# Peripherals.net
KiCad netlist of a schematic drawn in Altium Designer
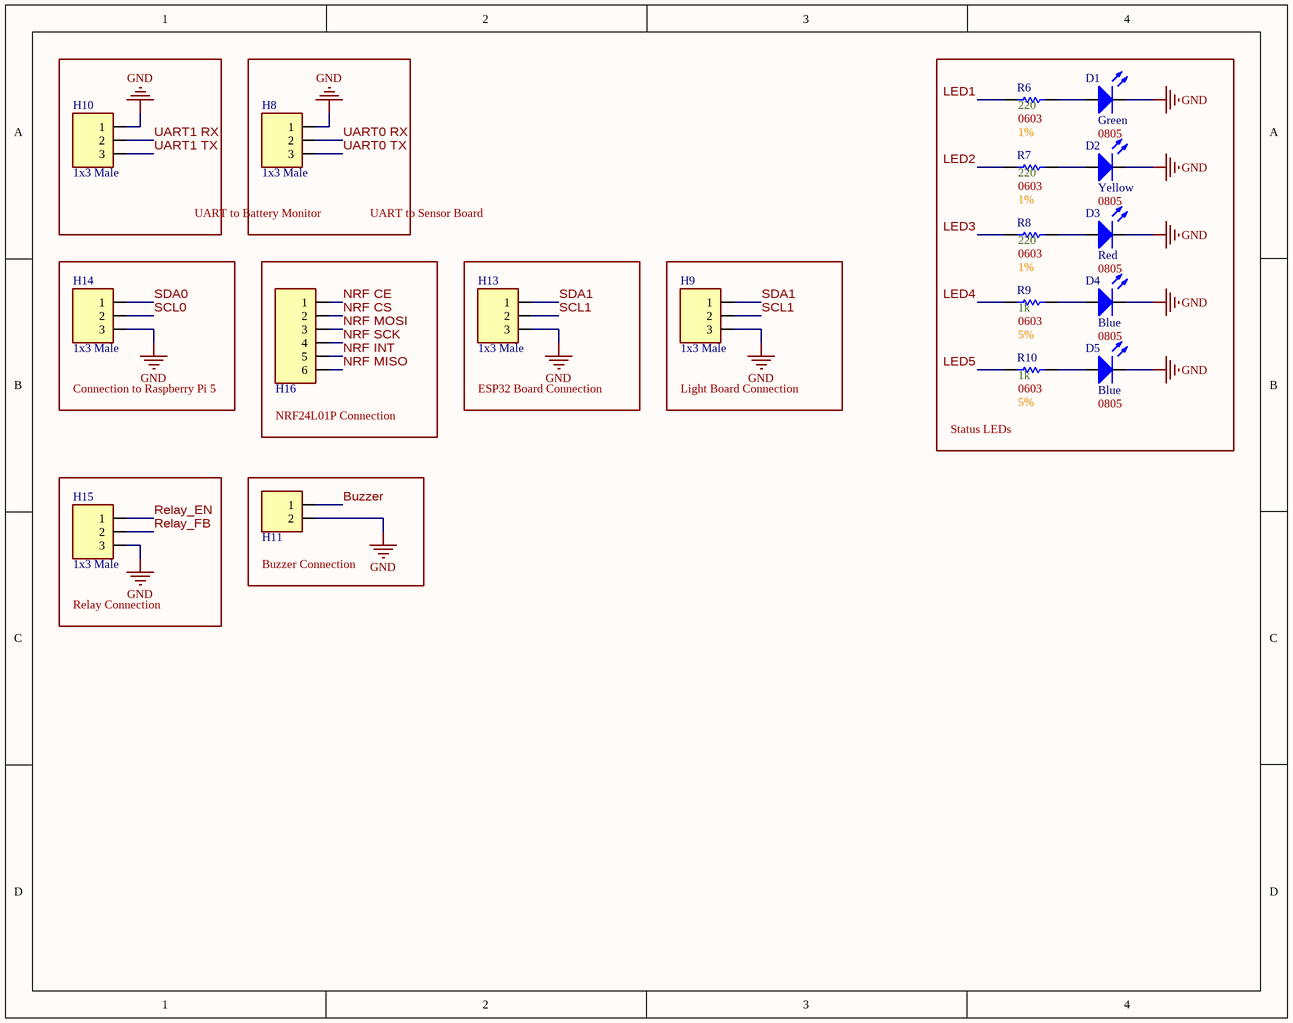
[diagram p0: Peripherals.SchDoc]

(export (version "E")
  (design (tool "Eeschema 10.0.6"))
  (components
    (comp (ref "D1")
      (value "SMD LED")
      (footprint "[LED] SMD 0805")
      (description "Generic")
      (fields (field (name "COLOR") "Green") (field (name "SIZE PACKAGE") "0805"))
      (libsource (lib "RADM Components") (part "[LED] SMD"))
    )
    (comp (ref "D2")
      (value "SMD LED")
      (footprint "[LED] SMD 0805")
      (description "Generic")
      (fields (field (name "COLOR") "Yellow") (field (name "SIZE PACKAGE") "0805"))
      (libsource (lib "RADM Components") (part "[LED] SMD"))
    )
    (comp (ref "D3")
      (value "SMD LED")
      (footprint "[LED] SMD 0805")
      (description "Generic")
      (fields (field (name "COLOR") "Red") (field (name "SIZE PACKAGE") "0805"))
      (libsource (lib "RADM Components") (part "[LED] SMD"))
    )
    (comp (ref "D4")
      (value "SMD LED")
      (footprint "[LED] SMD 0805")
      (description "Generic")
      (fields (field (name "COLOR") "Blue") (field (name "SIZE PACKAGE") "0805"))
      (libsource (lib "RADM Components") (part "[LED] SMD"))
    )
    (comp (ref "D5")
      (value "SMD LED")
      (footprint "[LED] SMD 0805")
      (description "Generic")
      (fields (field (name "COLOR") "Blue") (field (name "SIZE PACKAGE") "0805"))
      (libsource (lib "RADM Components") (part "[LED] SMD"))
    )
    (comp (ref "H8")
      (value "1x3 Male")
      (footprint "[Header] Shrouded 1x3 Male")
      (description "070543-0037\r\nMates with 005057-9403")
      (libsource (lib "RADM Connectors") (part "[Header] Shrouded 1x3 Male"))
    )
    (comp (ref "H9")
      (value "1x3 Male")
      (footprint "[Header] Shrouded 1x3 Male")
      (description "070543-0037\r\nMates with 005057-9403")
      (libsource (lib "RADM Connectors") (part "[Header] Shrouded 1x3 Male"))
    )
    (comp (ref "H10")
      (value "1x3 Male")
      (footprint "[Header] Shrouded 1x3 Male")
      (description "070543-0037\r\nMates with 005057-9403")
      (libsource (lib "RADM Connectors") (part "[Header] Shrouded 1x3 Male"))
    )
    (comp (ref "H11")
      (value "1x2 Male")
      (footprint "[Header] Shrouded 1x2 Male")
      (description "0705430036\r\nMates with 0050579402")
      (libsource (lib "RADM Connectors") (part "[Header] Shrouded 1x2 Male"))
    )
    (comp (ref "H13")
      (value "1x3 Male")
      (footprint "[Header] Shrouded 1x3 Male")
      (description "070543-0037\r\nMates with 005057-9403")
      (libsource (lib "RADM Connectors") (part "[Header] Shrouded 1x3 Male"))
    )
    (comp (ref "H14")
      (value "1x3 Male")
      (footprint "[Header] Shrouded 1x3 Male")
      (description "070543-0037\r\nMates with 005057-9403")
      (libsource (lib "RADM Connectors") (part "[Header] Shrouded 1x3 Male"))
    )
    (comp (ref "H15")
      (value "1x3 Male")
      (footprint "[Header] Shrouded 1x3 Male")
      (description "070543-0037\r\nMates with 005057-9403")
      (libsource (lib "RADM Connectors") (part "[Header] Shrouded 1x3 Male"))
    )
    (comp (ref "H16")
      (value "[Header] Shrouded 1x6 Male")
      (footprint "[Header] Shrouded 1x6 Male")
      (description "0705430005\r\nMates with 0050579406")
      (libsource (lib "RADM Connectors") (part "[Header] Shrouded 1x6 Male"))
    )
    (comp (ref "R6")
      (value "[Res] SMD Resistor")
      (footprint "[Res] SMD 0603")
      (description "Generic")
      (fields
        (field (name "RESISTANCE") "220")
        (field (name "SIZE PACKAGE") "0603")
        (field (name "TOLERANCE") "1%")
      )
      (libsource (lib "RADM Components") (part "[Res] SMD Resistor"))
    )
    (comp (ref "R7")
      (value "[Res] SMD Resistor")
      (footprint "[Res] SMD 0603")
      (description "Generic")
      (fields
        (field (name "RESISTANCE") "220")
        (field (name "SIZE PACKAGE") "0603")
        (field (name "TOLERANCE") "1%")
      )
      (libsource (lib "RADM Components") (part "[Res] SMD Resistor"))
    )
    (comp (ref "R8")
      (value "[Res] SMD Resistor")
      (footprint "[Res] SMD 0603")
      (description "Generic")
      (fields
        (field (name "RESISTANCE") "220")
        (field (name "SIZE PACKAGE") "0603")
        (field (name "TOLERANCE") "1%")
      )
      (libsource (lib "RADM Components") (part "[Res] SMD Resistor"))
    )
    (comp (ref "R9")
      (value "[Res] SMD Resistor")
      (footprint "[Res] SMD 0603")
      (description "Generic")
      (fields
        (field (name "RESISTANCE") "1k")
        (field (name "SIZE PACKAGE") "0603")
        (field (name "TOLERANCE") "5%")
      )
      (libsource (lib "RADM Components") (part "[Res] SMD Resistor"))
    )
    (comp (ref "R10")
      (value "[Res] SMD Resistor")
      (footprint "[Res] SMD 0603")
      (description "Generic")
      (fields
        (field (name "RESISTANCE") "1k")
        (field (name "SIZE PACKAGE") "0603")
        (field (name "TOLERANCE") "5%")
      )
      (libsource (lib "RADM Components") (part "[Res] SMD Resistor"))
    )
  )
  (nets
    (net (code "1") (name "/Buzzer") (class "Default")
      (node (ref "H11") (pin "1") (pinfunction "1_1") (pintype "passive"))
    )
    (net (code "2") (name "/LED1") (class "Default")
      (node (ref "R6") (pin "2") (pinfunction "2_2") (pintype "passive"))
    )
    (net (code "3") (name "/LED2") (class "Default")
      (node (ref "R7") (pin "2") (pinfunction "2_2") (pintype "passive"))
    )
    (net (code "4") (name "/LED3") (class "Default")
      (node (ref "R8") (pin "2") (pinfunction "2_2") (pintype "passive"))
    )
    (net (code "5") (name "/LED4") (class "Default")
      (node (ref "R9") (pin "2") (pinfunction "2_2") (pintype "passive"))
    )
    (net (code "6") (name "/LED5") (class "Default")
      (node (ref "R10") (pin "2") (pinfunction "2_2") (pintype "passive"))
    )
    (net (code "7") (name "/NRF CE") (class "Default")
      (node (ref "H16") (pin "1") (pinfunction "1_1") (pintype "passive"))
    )
    (net (code "8") (name "/NRF CS") (class "Default")
      (node (ref "H16") (pin "2") (pinfunction "2_2") (pintype "passive"))
    )
    (net (code "9") (name "/NRF INT") (class "Default")
      (node (ref "H16") (pin "5") (pinfunction "5_5") (pintype "passive"))
    )
    (net (code "10") (name "/NRF MISO") (class "Default")
      (node (ref "H16") (pin "6") (pinfunction "6_6") (pintype "passive"))
    )
    (net (code "11") (name "/NRF MOSI") (class "Default")
      (node (ref "H16") (pin "3") (pinfunction "3_3") (pintype "passive"))
    )
    (net (code "12") (name "/NRF SCK") (class "Default")
      (node (ref "H16") (pin "4") (pinfunction "4_4") (pintype "passive"))
    )
    (net (code "13") (name "/Relay_EN") (class "Default")
      (node (ref "H15") (pin "1") (pinfunction "1_1") (pintype "passive"))
    )
    (net (code "14") (name "/Relay_FB") (class "Default")
      (node (ref "H15") (pin "2") (pinfunction "2_2") (pintype "passive"))
    )
    (net (code "15") (name "/SCL0") (class "Default")
      (node (ref "H14") (pin "2") (pinfunction "2_2") (pintype "passive"))
    )
    (net (code "16") (name "/SCL1") (class "Default")
      (node (ref "H13") (pin "2") (pinfunction "2_2") (pintype "passive"))
      (node (ref "H9") (pin "2") (pinfunction "2_2") (pintype "passive"))
    )
    (net (code "17") (name "/SDA0") (class "Default")
      (node (ref "H14") (pin "1") (pinfunction "1_1") (pintype "passive"))
    )
    (net (code "18") (name "/SDA1") (class "Default")
      (node (ref "H13") (pin "1") (pinfunction "1_1") (pintype "passive"))
      (node (ref "H9") (pin "1") (pinfunction "1_1") (pintype "passive"))
    )
    (net (code "19") (name "/UART0 RX") (class "Default")
      (node (ref "H8") (pin "2") (pinfunction "2_2") (pintype "passive"))
    )
    (net (code "20") (name "/UART0 TX") (class "Default")
      (node (ref "H8") (pin "3") (pinfunction "3_3") (pintype "passive"))
    )
    (net (code "21") (name "/UART1 RX") (class "Default")
      (node (ref "H10") (pin "2") (pinfunction "2_2") (pintype "passive"))
    )
    (net (code "22") (name "/UART1 TX") (class "Default")
      (node (ref "H10") (pin "3") (pinfunction "3_3") (pintype "passive"))
    )
    (net (code "23") (name "GND") (class "Default")
      (node (ref "D1") (pin "2") (pinfunction "Cathode_2") (pintype "passive"))
      (node (ref "D2") (pin "2") (pinfunction "Cathode_2") (pintype "passive"))
      (node (ref "D3") (pin "2") (pinfunction "Cathode_2") (pintype "passive"))
      (node (ref "D4") (pin "2") (pinfunction "Cathode_2") (pintype "passive"))
      (node (ref "D5") (pin "2") (pinfunction "Cathode_2") (pintype "passive"))
      (node (ref "H10") (pin "1") (pinfunction "1_1") (pintype "passive"))
      (node (ref "H11") (pin "2") (pinfunction "2_2") (pintype "passive"))
      (node (ref "H13") (pin "3") (pinfunction "3_3") (pintype "passive"))
      (node (ref "H14") (pin "3") (pinfunction "3_3") (pintype "passive"))
      (node (ref "H15") (pin "3") (pinfunction "3_3") (pintype "passive"))
      (node (ref "H8") (pin "1") (pinfunction "1_1") (pintype "passive"))
      (node (ref "H9") (pin "3") (pinfunction "3_3") (pintype "passive"))
    )
    (net (code "24") (name "Net-(D1-Anode)") (class "Default")
      (node (ref "D1") (pin "1") (pinfunction "Anode_1") (pintype "passive"))
      (node (ref "R6") (pin "1") (pinfunction "1_1") (pintype "passive"))
    )
    (net (code "25") (name "Net-(D2-Anode)") (class "Default")
      (node (ref "D2") (pin "1") (pinfunction "Anode_1") (pintype "passive"))
      (node (ref "R7") (pin "1") (pinfunction "1_1") (pintype "passive"))
    )
    (net (code "26") (name "Net-(D3-Anode)") (class "Default")
      (node (ref "D3") (pin "1") (pinfunction "Anode_1") (pintype "passive"))
      (node (ref "R8") (pin "1") (pinfunction "1_1") (pintype "passive"))
    )
    (net (code "27") (name "Net-(D4-Anode)") (class "Default")
      (node (ref "D4") (pin "1") (pinfunction "Anode_1") (pintype "passive"))
      (node (ref "R9") (pin "1") (pinfunction "1_1") (pintype "passive"))
    )
    (net (code "28") (name "Net-(D5-Anode)") (class "Default")
      (node (ref "D5") (pin "1") (pinfunction "Anode_1") (pintype "passive"))
      (node (ref "R10") (pin "1") (pinfunction "1_1") (pintype "passive"))
    )
  )
)
